# Triangulator-LM324.net
KiCad netlist of a schematic drawn in EAGLE
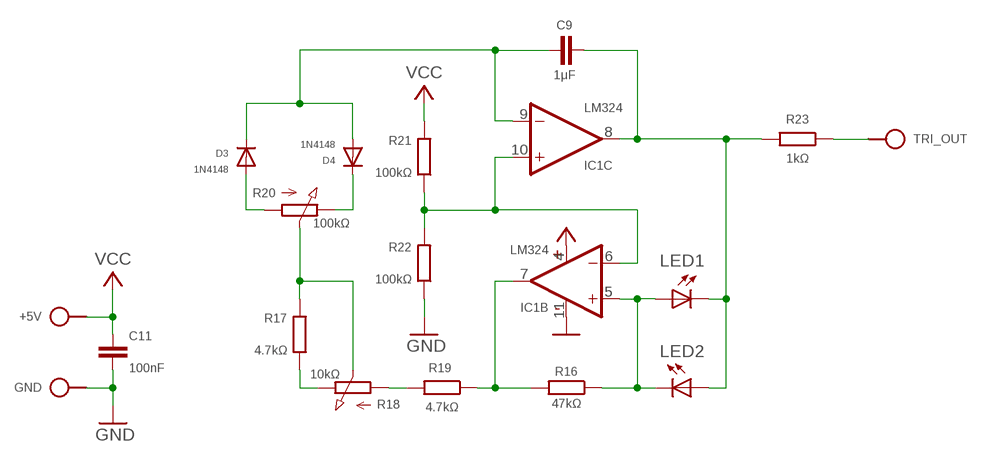
[diagram p0: schematic, sheet 1]

(export (version "E")
  (design (tool "Eeschema 10.0.6"))
  (components
    (comp (ref "+5V")
      (value "VCC")
      (footprint "eagle-import:SPAD")
      (libsource (lib "eagle-import") (part "SPAD"))
    )
    (comp (ref "C9")
      (value "1μF")
      (footprint "eagle-import:C050-024X044_V")
      (libsource (lib "eagle-import") (part "C050-024X044/V"))
    )
    (comp (ref "C11")
      (value "100nF")
      (footprint "eagle-import:C050-020X036")
      (libsource (lib "eagle-import") (part "C050-020X036"))
    )
    (comp (ref "D3")
      (value "1N4148")
      (footprint "eagle-import:DO34-7V")
      (libsource (lib "eagle-import") (part "1N414834-7V"))
    )
    (comp (ref "D4")
      (value "1N4148")
      (footprint "eagle-import:DO34-7V")
      (libsource (lib "eagle-import") (part "1N414834-7V"))
    )
    (comp (ref "GND")
      (value "GND")
      (footprint "eagle-import:SPAD")
      (libsource (lib "eagle-import") (part "SPAD"))
    )
    (comp (ref "IC1")
      (value "LM324")
      (footprint "eagle-import:DIL14")
      (libsource (lib "eagle-import") (part "LM324N"))
    )
    (comp (ref "LED1")
      (value "LED3MM")
      (footprint "eagle-import:LED3MM")
      (libsource (lib "eagle-import") (part "LED3MM"))
    )
    (comp (ref "LED2")
      (value "LED3MM")
      (footprint "eagle-import:LED3MM")
      (libsource (lib "eagle-import") (part "LED3MM"))
    )
    (comp (ref "R16")
      (value "47kΩ")
      (footprint "eagle-import:0202_7-V")
      (libsource (lib "eagle-import") (part "R0202/7-V"))
    )
    (comp (ref "R17")
      (value "4.7kΩ")
      (footprint "eagle-import:0202_7")
      (libsource (lib "eagle-import") (part "R0202/7"))
    )
    (comp (ref "R18")
      (value "10kΩ")
      (footprint "eagle-import:POT")
      (libsource (lib "eagle-import") (part "POT"))
    )
    (comp (ref "R19")
      (value "4.7kΩ")
      (footprint "eagle-import:0202_7-V")
      (libsource (lib "eagle-import") (part "R0202/7-V"))
    )
    (comp (ref "R20")
      (value "100kΩ")
      (footprint "eagle-import:POT")
      (libsource (lib "eagle-import") (part "POT"))
    )
    (comp (ref "R21")
      (value "100kΩ")
      (footprint "eagle-import:0202_7-V")
      (libsource (lib "eagle-import") (part "R0202/7-V"))
    )
    (comp (ref "R22")
      (value "100kΩ")
      (footprint "eagle-import:0202_7-V")
      (libsource (lib "eagle-import") (part "R0202/7-V"))
    )
    (comp (ref "R23")
      (value "1kΩ")
      (footprint "eagle-import:0202_7-V")
      (libsource (lib "eagle-import") (part "R0202/7-V"))
    )
    (comp (ref "TRI_OUT")
      (value "TRIANGLE")
      (footprint "eagle-import:SPAD")
      (libsource (lib "eagle-import") (part "SPAD"))
    )
  )
  (nets
    (net (code "1") (name "GND") (class "Default")
      (node (ref "C11") (pin "2") (pinfunction "2_2") (pintype "passive"))
      (node (ref "GND") (pin "1") (pinfunction "P$1_1") (pintype "bidirectional"))
      (node (ref "IC1") (pin "11") (pinfunction "V-_11") (pintype "power_in"))
      (node (ref "R22") (pin "1") (pinfunction "1_1") (pintype "passive"))
    )
    (net (code "2") (name "Net-(IC1B-+IN)") (class "Default")
      (node (ref "IC1") (pin "5") (pinfunction "+IN_5") (pintype "input"))
      (node (ref "LED1") (pin "A") (pinfunction "A_A") (pintype "passive"))
      (node (ref "LED2") (pin "K") (pinfunction "C_K") (pintype "passive"))
      (node (ref "R16") (pin "1") (pinfunction "1_1") (pintype "passive"))
    )
    (net (code "3") (name "Net-(IC1B--IN)") (class "Default")
      (node (ref "IC1") (pin "10") (pinfunction "+IN_10") (pintype "input"))
      (node (ref "IC1") (pin "6") (pinfunction "-IN_6") (pintype "input"))
      (node (ref "R21") (pin "1") (pinfunction "1_1") (pintype "passive"))
      (node (ref "R22") (pin "2") (pinfunction "2_2") (pintype "passive"))
    )
    (net (code "4") (name "Net-(IC1B-OUT)") (class "Default")
      (node (ref "IC1") (pin "7") (pinfunction "OUT_7") (pintype "output"))
      (node (ref "R16") (pin "2") (pinfunction "2_2") (pintype "passive"))
      (node (ref "R19") (pin "1") (pinfunction "1_1") (pintype "passive"))
    )
    (net (code "5") (name "Net-(IC1C--IN)") (class "Default")
      (node (ref "C9") (pin "1") (pinfunction "1_1") (pintype "passive"))
      (node (ref "D3") (pin "C") (pinfunction "C_C") (pintype "passive"))
      (node (ref "D4") (pin "A") (pinfunction "A_A") (pintype "passive"))
      (node (ref "IC1") (pin "9") (pinfunction "-IN_9") (pintype "input"))
    )
    (net (code "6") (name "Net-(IC1C-OUT)") (class "Default")
      (node (ref "C9") (pin "2") (pinfunction "2_2") (pintype "passive"))
      (node (ref "IC1") (pin "8") (pinfunction "OUT_8") (pintype "output"))
      (node (ref "LED1") (pin "K") (pinfunction "C_K") (pintype "passive"))
      (node (ref "LED2") (pin "A") (pinfunction "A_A") (pintype "passive"))
      (node (ref "R23") (pin "2") (pinfunction "2_2") (pintype "passive"))
    )
    (net (code "7") (name "Net-(R18-A)") (class "Default")
      (node (ref "R18") (pin "1") (pinfunction "A_1") (pintype "passive"))
      (node (ref "R19") (pin "2") (pinfunction "2_2") (pintype "passive"))
    )
    (net (code "8") (name "Net-(R18-E)") (class "Default")
      (node (ref "R17") (pin "1") (pinfunction "1_1") (pintype "passive"))
      (node (ref "R18") (pin "3") (pinfunction "E_3") (pintype "passive"))
    )
    (net (code "9") (name "Net-(R18-S)") (class "Default")
      (node (ref "R17") (pin "2") (pinfunction "2_2") (pintype "passive"))
      (node (ref "R18") (pin "2") (pinfunction "S_2") (pintype "passive"))
      (node (ref "R20") (pin "2") (pinfunction "S_2") (pintype "passive"))
    )
    (net (code "10") (name "Net-(R20-A)") (class "Default")
      (node (ref "D3") (pin "A") (pinfunction "A_A") (pintype "passive"))
      (node (ref "R20") (pin "1") (pinfunction "A_1") (pintype "passive"))
    )
    (net (code "11") (name "Net-(R20-E)") (class "Default")
      (node (ref "D4") (pin "C") (pinfunction "C_C") (pintype "passive"))
      (node (ref "R20") (pin "3") (pinfunction "E_3") (pintype "passive"))
    )
    (net (code "12") (name "Net-(TRI_OUT-P$1)") (class "Default")
      (node (ref "R23") (pin "1") (pinfunction "1_1") (pintype "passive"))
      (node (ref "TRI_OUT") (pin "1") (pinfunction "P$1_1") (pintype "bidirectional"))
    )
    (net (code "13") (name "VCC") (class "Default")
      (node (ref "+5V") (pin "1") (pinfunction "P$1_1") (pintype "bidirectional"))
      (node (ref "C11") (pin "1") (pinfunction "1_1") (pintype "passive"))
      (node (ref "IC1") (pin "4") (pinfunction "V+_4") (pintype "power_in"))
      (node (ref "R21") (pin "2") (pinfunction "2_2") (pintype "passive"))
    )
  )
)
